# V1.net
KiCad netlist of a schematic drawn in EAGLE
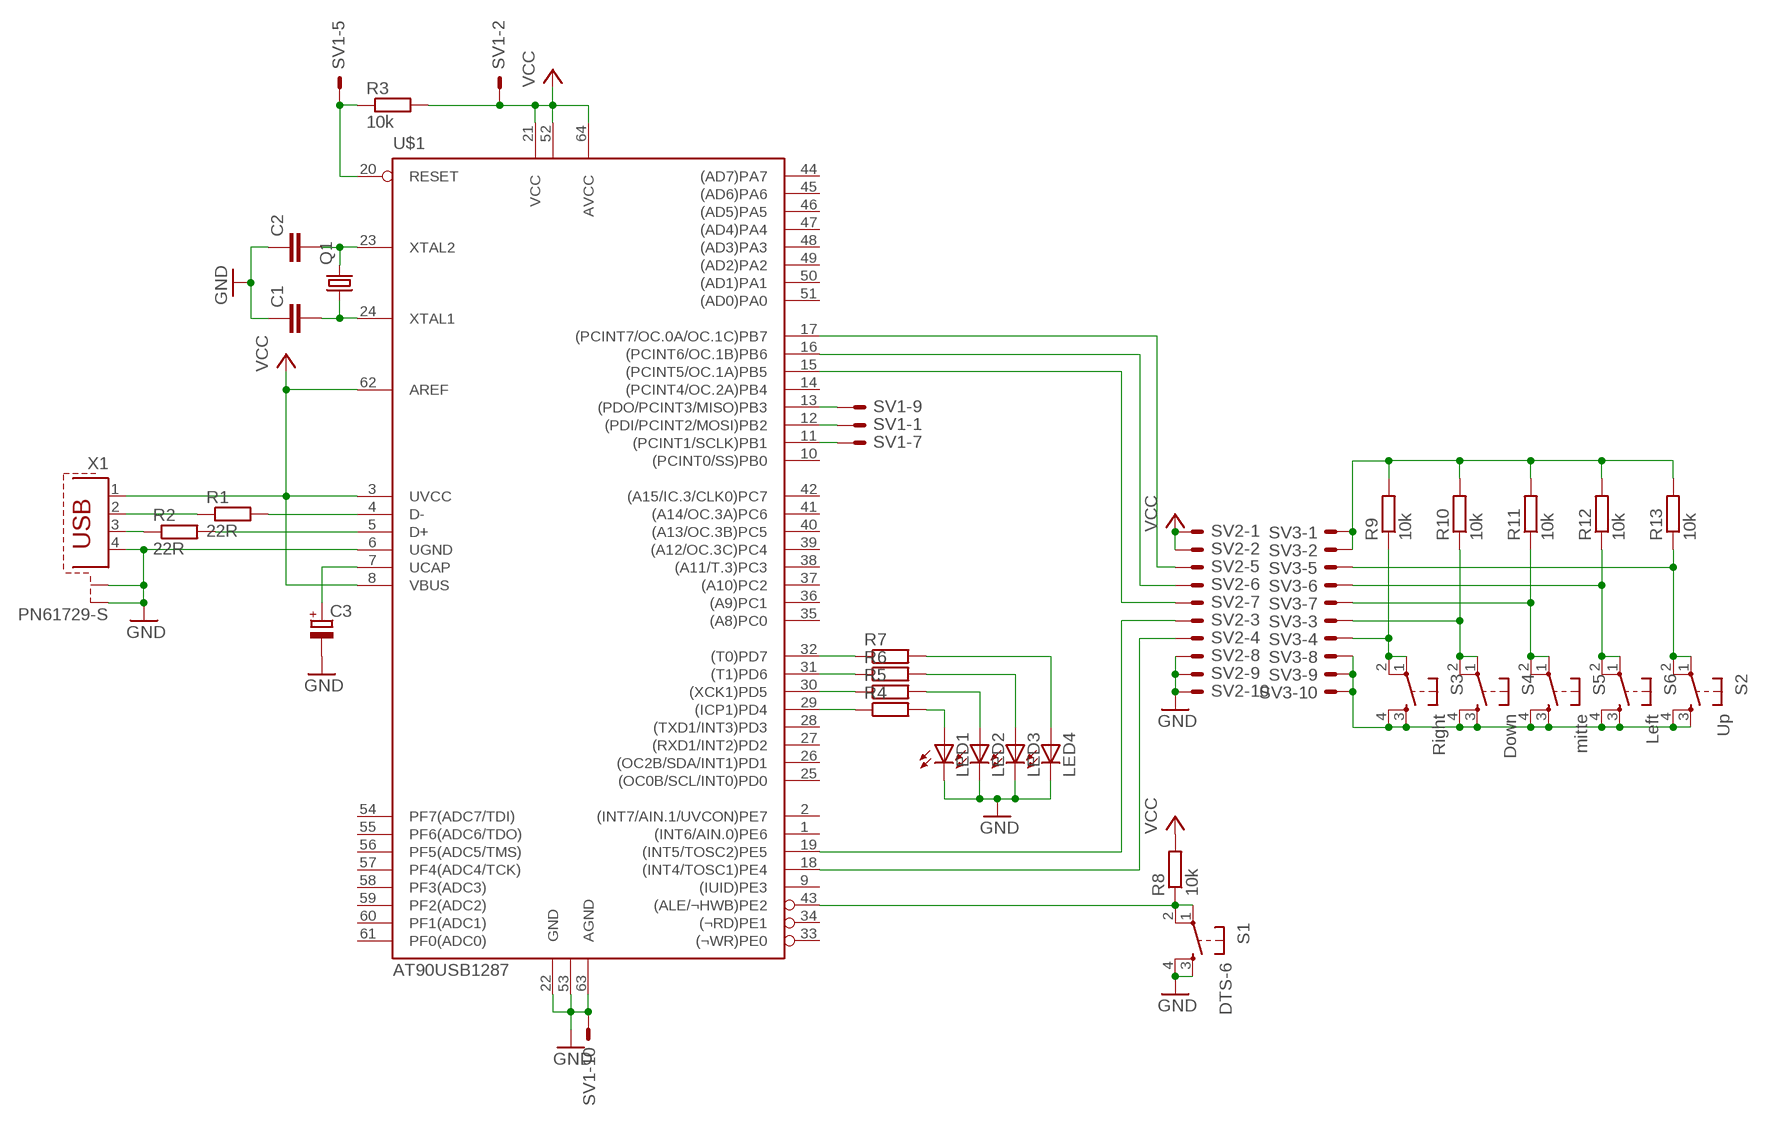
[diagram p0: schematic, sheet 1]

(export (version "E")
  (design (tool "Eeschema 10.0.6"))
  (components
    (comp (ref "C1")
      (value "C-EUC1206K")
      (footprint "eagle-import:C1206K")
      (libsource (lib "eagle-import") (part "C-EUC1206K"))
    )
    (comp (ref "C2")
      (value "C-EUC1206K")
      (footprint "eagle-import:C1206K")
      (libsource (lib "eagle-import") (part "C-EUC1206K"))
    )
    (comp (ref "C3")
      (value "CPOL-EUE2-5")
      (footprint "eagle-import:E2-5")
      (libsource (lib "eagle-import") (part "CPOL-EUE2-5"))
    )
    (comp (ref "LED1")
      (value "LED3MM")
      (footprint "eagle-import:LED3MM")
      (libsource (lib "eagle-import") (part "LED3MM"))
    )
    (comp (ref "LED2")
      (value "LED3MM")
      (footprint "eagle-import:LED3MM")
      (libsource (lib "eagle-import") (part "LED3MM"))
    )
    (comp (ref "LED3")
      (value "LED3MM")
      (footprint "eagle-import:LED3MM")
      (libsource (lib "eagle-import") (part "LED3MM"))
    )
    (comp (ref "LED4")
      (value "LED3MM")
      (footprint "eagle-import:LED3MM")
      (libsource (lib "eagle-import") (part "LED3MM"))
    )
    (comp (ref "Q1")
      (value "CRYSTALSM77H")
      (footprint "eagle-import:SM77H")
      (libsource (lib "eagle-import") (part "CRYSTALSM77H"))
    )
    (comp (ref "R1")
      (value "22R")
      (footprint "eagle-import:M1206")
      (libsource (lib "eagle-import") (part "R-EU_M1206"))
    )
    (comp (ref "R2")
      (value "22R")
      (footprint "eagle-import:M1206")
      (libsource (lib "eagle-import") (part "R-EU_M1206"))
    )
    (comp (ref "R3")
      (value "10k")
      (footprint "eagle-import:0207_10")
      (libsource (lib "eagle-import") (part "R-EU_0207/10"))
    )
    (comp (ref "R4")
      (value "R-EU_0207/10")
      (footprint "eagle-import:0207_10")
      (libsource (lib "eagle-import") (part "R-EU_0207/10"))
    )
    (comp (ref "R5")
      (value "R-EU_0207/10")
      (footprint "eagle-import:0207_10")
      (libsource (lib "eagle-import") (part "R-EU_0207/10"))
    )
    (comp (ref "R6")
      (value "R-EU_0207/10")
      (footprint "eagle-import:0207_10")
      (libsource (lib "eagle-import") (part "R-EU_0207/10"))
    )
    (comp (ref "R7")
      (value "R-EU_0207/10")
      (footprint "eagle-import:0207_10")
      (libsource (lib "eagle-import") (part "R-EU_0207/10"))
    )
    (comp (ref "R8")
      (value "10k")
      (footprint "eagle-import:M1206")
      (libsource (lib "eagle-import") (part "R-EU_M1206"))
    )
    (comp (ref "R9")
      (value "10k")
      (footprint "eagle-import:M1206")
      (libsource (lib "eagle-import") (part "R-EU_M1206"))
    )
    (comp (ref "R10")
      (value "10k")
      (footprint "eagle-import:M1206")
      (libsource (lib "eagle-import") (part "R-EU_M1206"))
    )
    (comp (ref "R11")
      (value "10k")
      (footprint "eagle-import:M1206")
      (libsource (lib "eagle-import") (part "R-EU_M1206"))
    )
    (comp (ref "R12")
      (value "10k")
      (footprint "eagle-import:M1206")
      (libsource (lib "eagle-import") (part "R-EU_M1206"))
    )
    (comp (ref "R13")
      (value "10k")
      (footprint "eagle-import:M1206")
      (libsource (lib "eagle-import") (part "R-EU_M1206"))
    )
    (comp (ref "S1")
      (value "DTS-6")
      (footprint "eagle-import:DTS-6")
      (libsource (lib "eagle-import") (part "DTS-6"))
    )
    (comp (ref "S2")
      (value "Up")
      (footprint "eagle-import:DTS-6")
      (libsource (lib "eagle-import") (part "DTS-6"))
    )
    (comp (ref "S3")
      (value "Right")
      (footprint "eagle-import:DTS-6")
      (libsource (lib "eagle-import") (part "DTS-6"))
    )
    (comp (ref "S4")
      (value "Down")
      (footprint "eagle-import:DTS-6")
      (libsource (lib "eagle-import") (part "DTS-6"))
    )
    (comp (ref "S5")
      (value "mitte")
      (footprint "eagle-import:DTS-6")
      (libsource (lib "eagle-import") (part "DTS-6"))
    )
    (comp (ref "S6")
      (value "Left")
      (footprint "eagle-import:DTS-6")
      (libsource (lib "eagle-import") (part "DTS-6"))
    )
    (comp (ref "SV1")
      (value "ML10E")
      (footprint "eagle-import:ML10")
      (libsource (lib "eagle-import") (part "ML10?E"))
    )
    (comp (ref "SV2")
      (value "ML10E")
      (footprint "eagle-import:ML10")
      (libsource (lib "eagle-import") (part "ML10?E"))
    )
    (comp (ref "SV3")
      (value "ML10E")
      (footprint "eagle-import:ML10")
      (libsource (lib "eagle-import") (part "ML10?E"))
    )
    (comp (ref "U$1")
      (value "AT90USB1287")
      (footprint "eagle-import:TQFP64")
      (libsource (lib "eagle-import") (part "AT90USB1287"))
    )
    (comp (ref "X1")
      (value "PN61729-S")
      (footprint "eagle-import:PN61729-S")
      (libsource (lib "eagle-import") (part "PN61729-S"))
    )
  )
  (nets
    (net (code "1") (name "GND") (class "Default")
      (node (ref "C1") (pin "1") (pinfunction "1_1") (pintype "passive"))
      (node (ref "C2") (pin "1") (pinfunction "1_1") (pintype "passive"))
      (node (ref "C3") (pin "-") (pinfunction "-_-") (pintype "passive"))
      (node (ref "LED1") (pin "K") (pinfunction "C_K") (pintype "passive"))
      (node (ref "LED2") (pin "K") (pinfunction "C_K") (pintype "passive"))
      (node (ref "LED3") (pin "K") (pinfunction "C_K") (pintype "passive"))
      (node (ref "LED4") (pin "K") (pinfunction "C_K") (pintype "passive"))
      (node (ref "S1") (pin "3") (pinfunction "3_3") (pintype "passive"))
      (node (ref "S1") (pin "4") (pinfunction "4_4") (pintype "passive"))
      (node (ref "SV1") (pin "10") (pinfunction "S_10") (pintype "passive"))
      (node (ref "SV2") (pin "10") (pinfunction "S_10") (pintype "passive"))
      (node (ref "SV2") (pin "8") (pinfunction "S_8") (pintype "passive"))
      (node (ref "SV2") (pin "9") (pinfunction "S_9") (pintype "passive"))
      (node (ref "U$1") (pin "22") (pinfunction "GND_22") (pintype "power_in"))
      (node (ref "U$1") (pin "53") (pinfunction "GND1_53") (pintype "power_in"))
      (node (ref "U$1") (pin "6") (pinfunction "UGND_6") (pintype "bidirectional"))
      (node (ref "U$1") (pin "63") (pinfunction "AGND_63") (pintype "bidirectional"))
      (node (ref "X1") (pin "4") (pinfunction "4_4") (pintype "passive"))
      (node (ref "X1") (pin "S1") (pinfunction "S1_S1") (pintype "passive"))
      (node (ref "X1") (pin "S2") (pinfunction "S2_S2") (pintype "passive"))
    )
    (net (code "2") (name "Net-(LED1-PadA)") (class "Default")
      (node (ref "LED1") (pin "A") (pinfunction "A_A") (pintype "passive"))
      (node (ref "R4") (pin "2") (pinfunction "2_2") (pintype "passive"))
    )
    (net (code "3") (name "Net-(LED2-PadA)") (class "Default")
      (node (ref "LED2") (pin "A") (pinfunction "A_A") (pintype "passive"))
      (node (ref "R5") (pin "2") (pinfunction "2_2") (pintype "passive"))
    )
    (net (code "4") (name "Net-(LED3-PadA)") (class "Default")
      (node (ref "LED3") (pin "A") (pinfunction "A_A") (pintype "passive"))
      (node (ref "R6") (pin "2") (pinfunction "2_2") (pintype "passive"))
    )
    (net (code "5") (name "Net-(LED4-PadA)") (class "Default")
      (node (ref "LED4") (pin "A") (pinfunction "A_A") (pintype "passive"))
      (node (ref "R7") (pin "2") (pinfunction "2_2") (pintype "passive"))
    )
    (net (code "6") (name "Net-(Q1-2)") (class "Default")
      (node (ref "C2") (pin "2") (pinfunction "2_2") (pintype "passive"))
      (node (ref "Q1") (pin "3") (pinfunction "2_3") (pintype "passive"))
      (node (ref "U$1") (pin "23") (pinfunction "XTAL2_23") (pintype "bidirectional"))
    )
    (net (code "7") (name "Net-(R1-Pad1)") (class "Default")
      (node (ref "R1") (pin "1") (pinfunction "1_1") (pintype "passive"))
      (node (ref "X1") (pin "2") (pinfunction "2_2") (pintype "passive"))
    )
    (net (code "8") (name "Net-(R2-Pad1)") (class "Default")
      (node (ref "R2") (pin "1") (pinfunction "1_1") (pintype "passive"))
      (node (ref "X1") (pin "3") (pinfunction "3_3") (pintype "passive"))
    )
    (net (code "9") (name "Net-(SV1A-S)") (class "Default")
      (node (ref "SV1") (pin "1") (pinfunction "S_1") (pintype "passive"))
      (node (ref "U$1") (pin "12") (pinfunction "(PDI/PCINT2/MOSI)PB2_12") (pintype "bidirectional"))
    )
    (net (code "10") (name "Net-(SV1F-S)") (class "Default")
      (node (ref "R3") (pin "1") (pinfunction "1_1") (pintype "passive"))
      (node (ref "SV1") (pin "5") (pinfunction "S_5") (pintype "passive"))
      (node (ref "U$1") (pin "20") (pinfunction "RESET_20") (pintype "input"))
    )
    (net (code "11") (name "Net-(SV1H-S)") (class "Default")
      (node (ref "SV1") (pin "7") (pinfunction "S_7") (pintype "passive"))
      (node (ref "U$1") (pin "11") (pinfunction "(PCINT1/SCLK)PB1_11") (pintype "bidirectional"))
    )
    (net (code "12") (name "Net-(SV1J-S)") (class "Default")
      (node (ref "SV1") (pin "9") (pinfunction "S_9") (pintype "passive"))
      (node (ref "U$1") (pin "13") (pinfunction "(PDO/PCINT3/MISO)PB3_13") (pintype "bidirectional"))
    )
    (net (code "13") (name "Net-(SV2D-S)") (class "Default")
      (node (ref "SV2") (pin "3") (pinfunction "S_3") (pintype "passive"))
      (node (ref "U$1") (pin "19") (pinfunction "(INT5/TOSC2)PE5_19") (pintype "bidirectional"))
    )
    (net (code "14") (name "Net-(SV2E-S)") (class "Default")
      (node (ref "SV2") (pin "4") (pinfunction "S_4") (pintype "passive"))
      (node (ref "U$1") (pin "18") (pinfunction "(INT4/TOSC1)PE4_18") (pintype "bidirectional"))
    )
    (net (code "15") (name "Net-(SV2F-S)") (class "Default")
      (node (ref "SV2") (pin "5") (pinfunction "S_5") (pintype "passive"))
      (node (ref "U$1") (pin "17") (pinfunction "(PCINT7/OC.0A/OC.1C)PB7_17") (pintype "bidirectional"))
    )
    (net (code "16") (name "Net-(SV2G-S)") (class "Default")
      (node (ref "SV2") (pin "6") (pinfunction "S_6") (pintype "passive"))
      (node (ref "U$1") (pin "16") (pinfunction "(PCINT6/OC.1B)PB6_16") (pintype "bidirectional"))
    )
    (net (code "17") (name "Net-(SV2H-S)") (class "Default")
      (node (ref "SV2") (pin "7") (pinfunction "S_7") (pintype "passive"))
      (node (ref "U$1") (pin "15") (pinfunction "(PCINT5/OC.1A)PB5_15") (pintype "bidirectional"))
    )
    (net (code "18") (name "Net-(SV3A-S)") (class "Default")
      (node (ref "R10") (pin "2") (pinfunction "2_2") (pintype "passive"))
      (node (ref "R11") (pin "2") (pinfunction "2_2") (pintype "passive"))
      (node (ref "R12") (pin "2") (pinfunction "2_2") (pintype "passive"))
      (node (ref "R13") (pin "2") (pinfunction "2_2") (pintype "passive"))
      (node (ref "R9") (pin "2") (pinfunction "2_2") (pintype "passive"))
      (node (ref "SV3") (pin "1") (pinfunction "S_1") (pintype "passive"))
      (node (ref "SV3") (pin "2") (pinfunction "S_2") (pintype "passive"))
    )
    (net (code "19") (name "Net-(SV3B-S)") (class "Default")
      (node (ref "S2") (pin "3") (pinfunction "3_3") (pintype "passive"))
      (node (ref "S2") (pin "4") (pinfunction "4_4") (pintype "passive"))
      (node (ref "S3") (pin "3") (pinfunction "3_3") (pintype "passive"))
      (node (ref "S3") (pin "4") (pinfunction "4_4") (pintype "passive"))
      (node (ref "S4") (pin "3") (pinfunction "3_3") (pintype "passive"))
      (node (ref "S4") (pin "4") (pinfunction "4_4") (pintype "passive"))
      (node (ref "S5") (pin "3") (pinfunction "3_3") (pintype "passive"))
      (node (ref "S5") (pin "4") (pinfunction "4_4") (pintype "passive"))
      (node (ref "S6") (pin "3") (pinfunction "3_3") (pintype "passive"))
      (node (ref "S6") (pin "4") (pinfunction "4_4") (pintype "passive"))
      (node (ref "SV3") (pin "10") (pinfunction "S_10") (pintype "passive"))
      (node (ref "SV3") (pin "8") (pinfunction "S_8") (pintype "passive"))
      (node (ref "SV3") (pin "9") (pinfunction "S_9") (pintype "passive"))
    )
    (net (code "20") (name "Net-(SV3D-S)") (class "Default")
      (node (ref "R10") (pin "1") (pinfunction "1_1") (pintype "passive"))
      (node (ref "S4") (pin "1") (pinfunction "1_1") (pintype "passive"))
      (node (ref "S4") (pin "2") (pinfunction "2_2") (pintype "passive"))
      (node (ref "SV3") (pin "3") (pinfunction "S_3") (pintype "passive"))
    )
    (net (code "21") (name "Net-(SV3E-S)") (class "Default")
      (node (ref "R9") (pin "1") (pinfunction "1_1") (pintype "passive"))
      (node (ref "S3") (pin "1") (pinfunction "1_1") (pintype "passive"))
      (node (ref "S3") (pin "2") (pinfunction "2_2") (pintype "passive"))
      (node (ref "SV3") (pin "4") (pinfunction "S_4") (pintype "passive"))
    )
    (net (code "22") (name "Net-(SV3F-S)") (class "Default")
      (node (ref "R13") (pin "1") (pinfunction "1_1") (pintype "passive"))
      (node (ref "S2") (pin "1") (pinfunction "1_1") (pintype "passive"))
      (node (ref "S2") (pin "2") (pinfunction "2_2") (pintype "passive"))
      (node (ref "SV3") (pin "5") (pinfunction "S_5") (pintype "passive"))
    )
    (net (code "23") (name "Net-(SV3G-S)") (class "Default")
      (node (ref "R12") (pin "1") (pinfunction "1_1") (pintype "passive"))
      (node (ref "S6") (pin "1") (pinfunction "1_1") (pintype "passive"))
      (node (ref "S6") (pin "2") (pinfunction "2_2") (pintype "passive"))
      (node (ref "SV3") (pin "6") (pinfunction "S_6") (pintype "passive"))
    )
    (net (code "24") (name "Net-(SV3H-S)") (class "Default")
      (node (ref "R11") (pin "1") (pinfunction "1_1") (pintype "passive"))
      (node (ref "S5") (pin "1") (pinfunction "1_1") (pintype "passive"))
      (node (ref "S5") (pin "2") (pinfunction "2_2") (pintype "passive"))
      (node (ref "SV3") (pin "7") (pinfunction "S_7") (pintype "passive"))
    )
    (net (code "25") (name "Net-(U$1-(ALE{slash}¬HWB)PE2)") (class "Default")
      (node (ref "R8") (pin "1") (pinfunction "1_1") (pintype "passive"))
      (node (ref "S1") (pin "1") (pinfunction "1_1") (pintype "passive"))
      (node (ref "S1") (pin "2") (pinfunction "2_2") (pintype "passive"))
      (node (ref "U$1") (pin "43") (pinfunction "(ALE/¬HWB)PE2_43") (pintype "input"))
    )
    (net (code "26") (name "Net-(U$1-(ICP1)PD4)") (class "Default")
      (node (ref "R4") (pin "1") (pinfunction "1_1") (pintype "passive"))
      (node (ref "U$1") (pin "29") (pinfunction "(ICP1)PD4_29") (pintype "bidirectional"))
    )
    (net (code "27") (name "Net-(U$1-(T0)PD7)") (class "Default")
      (node (ref "R7") (pin "1") (pinfunction "1_1") (pintype "passive"))
      (node (ref "U$1") (pin "32") (pinfunction "(T0)PD7_32") (pintype "bidirectional"))
    )
    (net (code "28") (name "Net-(U$1-(T1)PD6)") (class "Default")
      (node (ref "R6") (pin "1") (pinfunction "1_1") (pintype "passive"))
      (node (ref "U$1") (pin "31") (pinfunction "(T1)PD6_31") (pintype "bidirectional"))
    )
    (net (code "29") (name "Net-(U$1-(XCK1)PD5)") (class "Default")
      (node (ref "R5") (pin "1") (pinfunction "1_1") (pintype "passive"))
      (node (ref "U$1") (pin "30") (pinfunction "(XCK1)PD5_30") (pintype "bidirectional"))
    )
    (net (code "30") (name "Net-(U$1-D+)") (class "Default")
      (node (ref "R2") (pin "2") (pinfunction "2_2") (pintype "passive"))
      (node (ref "U$1") (pin "5") (pinfunction "D+_5") (pintype "bidirectional"))
    )
    (net (code "31") (name "Net-(U$1-D-)") (class "Default")
      (node (ref "R1") (pin "2") (pinfunction "2_2") (pintype "passive"))
      (node (ref "U$1") (pin "4") (pinfunction "D-_4") (pintype "bidirectional"))
    )
    (net (code "32") (name "Net-(U$1-UCAP)") (class "Default")
      (node (ref "C3") (pin "+") (pinfunction "+_+") (pintype "passive"))
      (node (ref "U$1") (pin "7") (pinfunction "UCAP_7") (pintype "bidirectional"))
    )
    (net (code "33") (name "Net-(U$1-XTAL1)") (class "Default")
      (node (ref "C1") (pin "2") (pinfunction "2_2") (pintype "passive"))
      (node (ref "Q1") (pin "1") (pinfunction "1_1") (pintype "passive"))
      (node (ref "U$1") (pin "24") (pinfunction "XTAL1_24") (pintype "bidirectional"))
    )
    (net (code "34") (name "VCC") (class "Default")
      (node (ref "R3") (pin "2") (pinfunction "2_2") (pintype "passive"))
      (node (ref "R8") (pin "2") (pinfunction "2_2") (pintype "passive"))
      (node (ref "SV1") (pin "2") (pinfunction "S_2") (pintype "passive"))
      (node (ref "SV2") (pin "1") (pinfunction "S_1") (pintype "passive"))
      (node (ref "SV2") (pin "2") (pinfunction "S_2") (pintype "passive"))
      (node (ref "U$1") (pin "21") (pinfunction "VCC_21") (pintype "power_in"))
      (node (ref "U$1") (pin "3") (pinfunction "UVCC_3") (pintype "bidirectional"))
      (node (ref "U$1") (pin "52") (pinfunction "VCC1_52") (pintype "power_in"))
      (node (ref "U$1") (pin "62") (pinfunction "AREF_62") (pintype "bidirectional"))
      (node (ref "U$1") (pin "64") (pinfunction "AVCC_64") (pintype "bidirectional"))
      (node (ref "U$1") (pin "8") (pinfunction "VBUS_8") (pintype "bidirectional"))
      (node (ref "X1") (pin "1") (pinfunction "1_1") (pintype "passive"))
    )
    (net (code "35") (name "unconnected-(U$1-(A8)PC0-Pad35)") (class "Default")
      (node (ref "U$1") (pin "35") (pinfunction "(A8)PC0_35") (pintype "output"))
    )
    (net (code "36") (name "unconnected-(U$1-(A9)PC1-Pad36)") (class "Default")
      (node (ref "U$1") (pin "36") (pinfunction "(A9)PC1_36") (pintype "output"))
    )
    (net (code "37") (name "unconnected-(U$1-(A10)PC2-Pad37)") (class "Default")
      (node (ref "U$1") (pin "37") (pinfunction "(A10)PC2_37") (pintype "output"))
    )
    (net (code "38") (name "unconnected-(U$1-(A11{slash}T.3)PC3-Pad38)") (class "Default")
      (node (ref "U$1") (pin "38") (pinfunction "(A11/T.3)PC3_38") (pintype "output"))
    )
    (net (code "39") (name "unconnected-(U$1-(A12{slash}OC.3C)PC4-Pad39)") (class "Default")
      (node (ref "U$1") (pin "39") (pinfunction "(A12/OC.3C)PC4_39") (pintype "output"))
    )
    (net (code "40") (name "unconnected-(U$1-(A13{slash}OC.3B)PC5-Pad40)") (class "Default")
      (node (ref "U$1") (pin "40") (pinfunction "(A13/OC.3B)PC5_40") (pintype "output"))
    )
    (net (code "41") (name "unconnected-(U$1-(A14{slash}OC.3A)PC6-Pad41)") (class "Default")
      (node (ref "U$1") (pin "41") (pinfunction "(A14/OC.3A)PC6_41") (pintype "output"))
    )
    (net (code "42") (name "unconnected-(U$1-(A15{slash}IC.3{slash}CLK0)PC7-Pad42)") (class "Default")
      (node (ref "U$1") (pin "42") (pinfunction "(A15/IC.3/CLK0)PC7_42") (pintype "output"))
    )
    (net (code "43") (name "unconnected-(U$1-(AD0)PA0-Pad51)") (class "Default")
      (node (ref "U$1") (pin "51") (pinfunction "(AD0)PA0_51") (pintype "bidirectional"))
    )
    (net (code "44") (name "unconnected-(U$1-(AD1)PA1-Pad50)") (class "Default")
      (node (ref "U$1") (pin "50") (pinfunction "(AD1)PA1_50") (pintype "bidirectional"))
    )
    (net (code "45") (name "unconnected-(U$1-(AD2)PA2-Pad49)") (class "Default")
      (node (ref "U$1") (pin "49") (pinfunction "(AD2)PA2_49") (pintype "bidirectional"))
    )
    (net (code "46") (name "unconnected-(U$1-(AD3)PA3-Pad48)") (class "Default")
      (node (ref "U$1") (pin "48") (pinfunction "(AD3)PA3_48") (pintype "bidirectional"))
    )
    (net (code "47") (name "unconnected-(U$1-(AD4)PA4-Pad47)") (class "Default")
      (node (ref "U$1") (pin "47") (pinfunction "(AD4)PA4_47") (pintype "bidirectional"))
    )
    (net (code "48") (name "unconnected-(U$1-(AD5)PA5-Pad46)") (class "Default")
      (node (ref "U$1") (pin "46") (pinfunction "(AD5)PA5_46") (pintype "bidirectional"))
    )
    (net (code "49") (name "unconnected-(U$1-(AD6)PA6-Pad45)") (class "Default")
      (node (ref "U$1") (pin "45") (pinfunction "(AD6)PA6_45") (pintype "bidirectional"))
    )
    (net (code "50") (name "unconnected-(U$1-(AD7)PA7-Pad44)") (class "Default")
      (node (ref "U$1") (pin "44") (pinfunction "(AD7)PA7_44") (pintype "bidirectional"))
    )
    (net (code "51") (name "unconnected-(U$1-(INT6{slash}AIN.0)PE6-Pad1)") (class "Default")
      (node (ref "U$1") (pin "1") (pinfunction "(INT6/AIN.0)PE6_1") (pintype "bidirectional"))
    )
    (net (code "52") (name "unconnected-(U$1-(INT7{slash}AIN.1{slash}UVCON)PE7-Pad2)") (class "Default")
      (node (ref "U$1") (pin "2") (pinfunction "(INT7/AIN.1/UVCON)PE7_2") (pintype "bidirectional"))
    )
    (net (code "53") (name "unconnected-(U$1-(IUID)PE3-Pad9)") (class "Default")
      (node (ref "U$1") (pin "9") (pinfunction "(IUID)PE3_9") (pintype "bidirectional"))
    )
    (net (code "54") (name "unconnected-(U$1-(OC0B{slash}SCL{slash}INT0)PD0-Pad25)") (class "Default")
      (node (ref "U$1") (pin "25") (pinfunction "(OC0B/SCL/INT0)PD0_25") (pintype "bidirectional"))
    )
    (net (code "55") (name "unconnected-(U$1-(OC2B{slash}SDA{slash}INT1)PD1-Pad26)") (class "Default")
      (node (ref "U$1") (pin "26") (pinfunction "(OC2B/SDA/INT1)PD1_26") (pintype "bidirectional"))
    )
    (net (code "56") (name "unconnected-(U$1-(PCINT0{slash}SS)PB0-Pad10)") (class "Default")
      (node (ref "U$1") (pin "10") (pinfunction "(PCINT0/SS)PB0_10") (pintype "bidirectional"))
    )
    (net (code "57") (name "unconnected-(U$1-(PCINT4{slash}OC.2A)PB4-Pad14)") (class "Default")
      (node (ref "U$1") (pin "14") (pinfunction "(PCINT4/OC.2A)PB4_14") (pintype "bidirectional"))
    )
    (net (code "58") (name "unconnected-(U$1-(RXD1{slash}INT2)PD2-Pad27)") (class "Default")
      (node (ref "U$1") (pin "27") (pinfunction "(RXD1/INT2)PD2_27") (pintype "bidirectional"))
    )
    (net (code "59") (name "unconnected-(U$1-(TXD1{slash}INT3)PD3-Pad28)") (class "Default")
      (node (ref "U$1") (pin "28") (pinfunction "(TXD1/INT3)PD3_28") (pintype "bidirectional"))
    )
    (net (code "60") (name "unconnected-(U$1-(¬RD)PE1-Pad34)") (class "Default")
      (node (ref "U$1") (pin "34") (pinfunction "(¬RD)PE1_34") (pintype "bidirectional"))
    )
    (net (code "61") (name "unconnected-(U$1-(¬WR)PE0-Pad33)") (class "Default")
      (node (ref "U$1") (pin "33") (pinfunction "(¬WR)PE0_33") (pintype "bidirectional"))
    )
    (net (code "62") (name "unconnected-(U$1-PF0(ADC0)-Pad61)") (class "Default")
      (node (ref "U$1") (pin "61") (pinfunction "PF0(ADC0)_61") (pintype "input"))
    )
    (net (code "63") (name "unconnected-(U$1-PF1(ADC1)-Pad60)") (class "Default")
      (node (ref "U$1") (pin "60") (pinfunction "PF1(ADC1)_60") (pintype "input"))
    )
    (net (code "64") (name "unconnected-(U$1-PF2(ADC2)-Pad59)") (class "Default")
      (node (ref "U$1") (pin "59") (pinfunction "PF2(ADC2)_59") (pintype "input"))
    )
    (net (code "65") (name "unconnected-(U$1-PF3(ADC3)-Pad58)") (class "Default")
      (node (ref "U$1") (pin "58") (pinfunction "PF3(ADC3)_58") (pintype "input"))
    )
    (net (code "66") (name "unconnected-(U$1-PF4(ADC4{slash}TCK)-Pad57)") (class "Default")
      (node (ref "U$1") (pin "57") (pinfunction "PF4(ADC4/TCK)_57") (pintype "input"))
    )
    (net (code "67") (name "unconnected-(U$1-PF5(ADC5{slash}TMS)-Pad56)") (class "Default")
      (node (ref "U$1") (pin "56") (pinfunction "PF5(ADC5/TMS)_56") (pintype "input"))
    )
    (net (code "68") (name "unconnected-(U$1-PF6(ADC6{slash}TDO)-Pad55)") (class "Default")
      (node (ref "U$1") (pin "55") (pinfunction "PF6(ADC6/TDO)_55") (pintype "input"))
    )
    (net (code "69") (name "unconnected-(U$1-PF7(ADC7{slash}TDI)-Pad54)") (class "Default")
      (node (ref "U$1") (pin "54") (pinfunction "PF7(ADC7/TDI)_54") (pintype "input"))
    )
  )
)
